# AUAV-X1_SENSORS_R1.net
KiCad netlist of a schematic drawn in Altium Designer
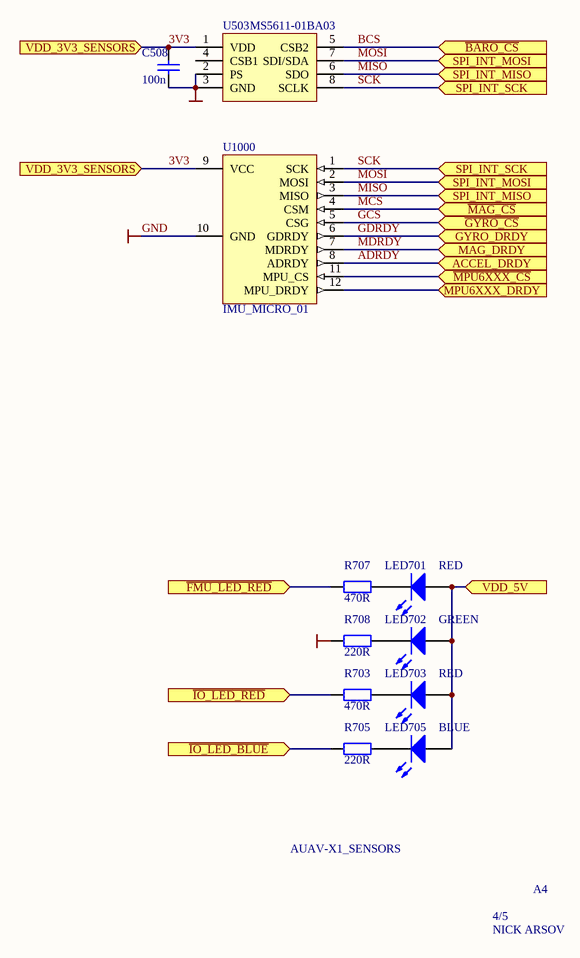
[diagram p0: AUAV-X1_SENSORS_R1.SchDoc]

(export (version "E")
  (design (tool "Eeschema 10.0.6"))
  (components
    (comp (ref "C508")
      (value "100n")
      (footprint "0402A")
      (description "Capacitor")
      (fields (field (name "PUBLISHER") "Altium Limited"))
      (libsource (lib "Miscellaneous Devices") (part "Cap"))
    )
    (comp (ref "LED701")
      (value "RED")
      (footprint "0603A")
      (description "Typical INFRARED GaAs LED")
      (fields (field (name "PUBLISHER") "Altium Limited"))
      (libsource (lib "Miscellaneous Devices") (part "LED0"))
    )
    (comp (ref "LED702")
      (value "GREEN")
      (footprint "0603A")
      (description "Typical INFRARED GaAs LED")
      (fields (field (name "PUBLISHER") "Altium Limited"))
      (libsource (lib "Miscellaneous Devices") (part "LED0"))
    )
    (comp (ref "LED703")
      (value "RED")
      (footprint "0603A")
      (description "Typical INFRARED GaAs LED")
      (fields (field (name "PUBLISHER") "Altium Limited"))
      (libsource (lib "Miscellaneous Devices") (part "LED0"))
    )
    (comp (ref "LED705")
      (value "BLUE")
      (footprint "0603A")
      (description "Typical INFRARED GaAs LED")
      (fields (field (name "PUBLISHER") "Altium Limited"))
      (libsource (lib "Miscellaneous Devices") (part "LED0"))
    )
    (comp (ref "R703")
      (value "470R")
      (footprint "0603A")
      (description "Resistor")
      (fields (field (name "PUBLISHER") "Altium Limited"))
      (libsource (lib "Miscellaneous Devices") (part "Res2"))
    )
    (comp (ref "R705")
      (value "220R")
      (footprint "0603A")
      (description "Resistor")
      (fields (field (name "PUBLISHER") "Altium Limited"))
      (libsource (lib "Miscellaneous Devices") (part "Res2"))
    )
    (comp (ref "R707")
      (value "470R")
      (footprint "0603A")
      (description "Resistor")
      (fields (field (name "PUBLISHER") "Altium Limited"))
      (libsource (lib "Miscellaneous Devices") (part "Res2"))
    )
    (comp (ref "R708")
      (value "220R")
      (footprint "0603A")
      (description "Resistor")
      (fields (field (name "PUBLISHER") "Altium Limited"))
      (libsource (lib "Miscellaneous Devices") (part "Res2"))
    )
    (comp (ref "U503")
      (value "MS5611-01BA03")
      (footprint "MS5611")
      (libsource (lib "My_Altium") (part "MS5611-01BA03"))
    )
    (comp (ref "U1000")
      (value "IMU_MICRO_01")
      (footprint "MicroIMU_01")
      (libsource (lib "My_Altium") (part "IMU_MICRO_01"))
    )
  )
  (nets
    (net (code "1") (name "/3V3") (class "Default")
      (node (ref "C508") (pin "2") (pinfunction "2_2") (pintype "passive"))
      (node (ref "U1000") (pin "9") (pinfunction "VCC_9") (pintype "power_in"))
      (node (ref "U503") (pin "1") (pinfunction "VDD_1") (pintype "power_in"))
    )
    (net (code "2") (name "/ADRDY") (class "Default")
      (node (ref "U1000") (pin "8") (pinfunction "ADRDY_8") (pintype "output"))
    )
    (net (code "3") (name "/BCS") (class "Default")
      (node (ref "U503") (pin "5") (pinfunction "CSB2_5") (pintype "passive"))
    )
    (net (code "4") (name "/GCS") (class "Default")
      (node (ref "U1000") (pin "5") (pinfunction "CSG_5") (pintype "input"))
    )
    (net (code "5") (name "/GDRDY") (class "Default")
      (node (ref "U1000") (pin "6") (pinfunction "GDRDY_6") (pintype "output"))
    )
    (net (code "6") (name "/MCS") (class "Default")
      (node (ref "U1000") (pin "4") (pinfunction "CSM_4") (pintype "input"))
    )
    (net (code "7") (name "/MDRDY") (class "Default")
      (node (ref "U1000") (pin "7") (pinfunction "MDRDY_7") (pintype "output"))
    )
    (net (code "8") (name "/MISO") (class "Default")
      (node (ref "U1000") (pin "3") (pinfunction "MISO_3") (pintype "output"))
      (node (ref "U503") (pin "6") (pinfunction "SDO_6") (pintype "passive"))
    )
    (net (code "9") (name "/MOSI") (class "Default")
      (node (ref "U1000") (pin "2") (pinfunction "MOSI_2") (pintype "input"))
      (node (ref "U503") (pin "7") (pinfunction "SDI/SDA_7") (pintype "passive"))
    )
    (net (code "10") (name "/MPU6XXX_DRDY") (class "Default")
      (node (ref "U1000") (pin "12") (pinfunction "MPU_DRDY_12") (pintype "output"))
    )
    (net (code "11") (name "/SCK") (class "Default")
      (node (ref "U1000") (pin "1") (pinfunction "SCK_1") (pintype "input"))
      (node (ref "U503") (pin "8") (pinfunction "SCLK_8") (pintype "passive"))
    )
    (net (code "12") (name "/VDD_5V") (class "Default")
      (node (ref "LED701") (pin "1") (pinfunction "A_1") (pintype "passive"))
      (node (ref "LED702") (pin "1") (pinfunction "A_1") (pintype "passive"))
      (node (ref "LED703") (pin "1") (pinfunction "A_1") (pintype "passive"))
      (node (ref "LED705") (pin "1") (pinfunction "A_1") (pintype "passive"))
    )
    (net (code "13") (name "/~{FMU_LED_RED}") (class "Default")
      (node (ref "R707") (pin "2") (pinfunction "2_2") (pintype "passive"))
    )
    (net (code "14") (name "/~{IO_LED_BLUE}") (class "Default")
      (node (ref "R705") (pin "2") (pinfunction "2_2") (pintype "passive"))
    )
    (net (code "15") (name "/~{IO_LED_RED}") (class "Default")
      (node (ref "R703") (pin "2") (pinfunction "2_2") (pintype "passive"))
    )
    (net (code "16") (name "/~{MPU6XXX_CS}") (class "Default")
      (node (ref "U1000") (pin "11") (pinfunction "MPU_CS_11") (pintype "input"))
    )
    (net (code "17") (name "GND") (class "Default")
      (node (ref "C508") (pin "1") (pinfunction "1_1") (pintype "passive"))
      (node (ref "R708") (pin "2") (pinfunction "2_2") (pintype "passive"))
      (node (ref "U1000") (pin "10") (pinfunction "GND_10") (pintype "power_in"))
      (node (ref "U503") (pin "2") (pinfunction "PS_2") (pintype "passive"))
      (node (ref "U503") (pin "3") (pinfunction "GND_3") (pintype "power_in"))
    )
    (net (code "18") (name "Net-(LED701-K)") (class "Default")
      (node (ref "LED701") (pin "2") (pinfunction "K_2") (pintype "passive"))
      (node (ref "R707") (pin "1") (pinfunction "1_1") (pintype "passive"))
    )
    (net (code "19") (name "Net-(LED702-K)") (class "Default")
      (node (ref "LED702") (pin "2") (pinfunction "K_2") (pintype "passive"))
      (node (ref "R708") (pin "1") (pinfunction "1_1") (pintype "passive"))
    )
    (net (code "20") (name "Net-(LED703-K)") (class "Default")
      (node (ref "LED703") (pin "2") (pinfunction "K_2") (pintype "passive"))
      (node (ref "R703") (pin "1") (pinfunction "1_1") (pintype "passive"))
    )
    (net (code "21") (name "Net-(LED705-K)") (class "Default")
      (node (ref "LED705") (pin "2") (pinfunction "K_2") (pintype "passive"))
      (node (ref "R705") (pin "1") (pinfunction "1_1") (pintype "passive"))
    )
    (net (code "22") (name "unconnected-(U503-CSB1-Pad4)") (class "Default")
      (node (ref "U503") (pin "4") (pinfunction "CSB1_4") (pintype "passive"))
    )
  )
)
